# mbed-interface.net
KiCad netlist of a schematic drawn in Altium Designer
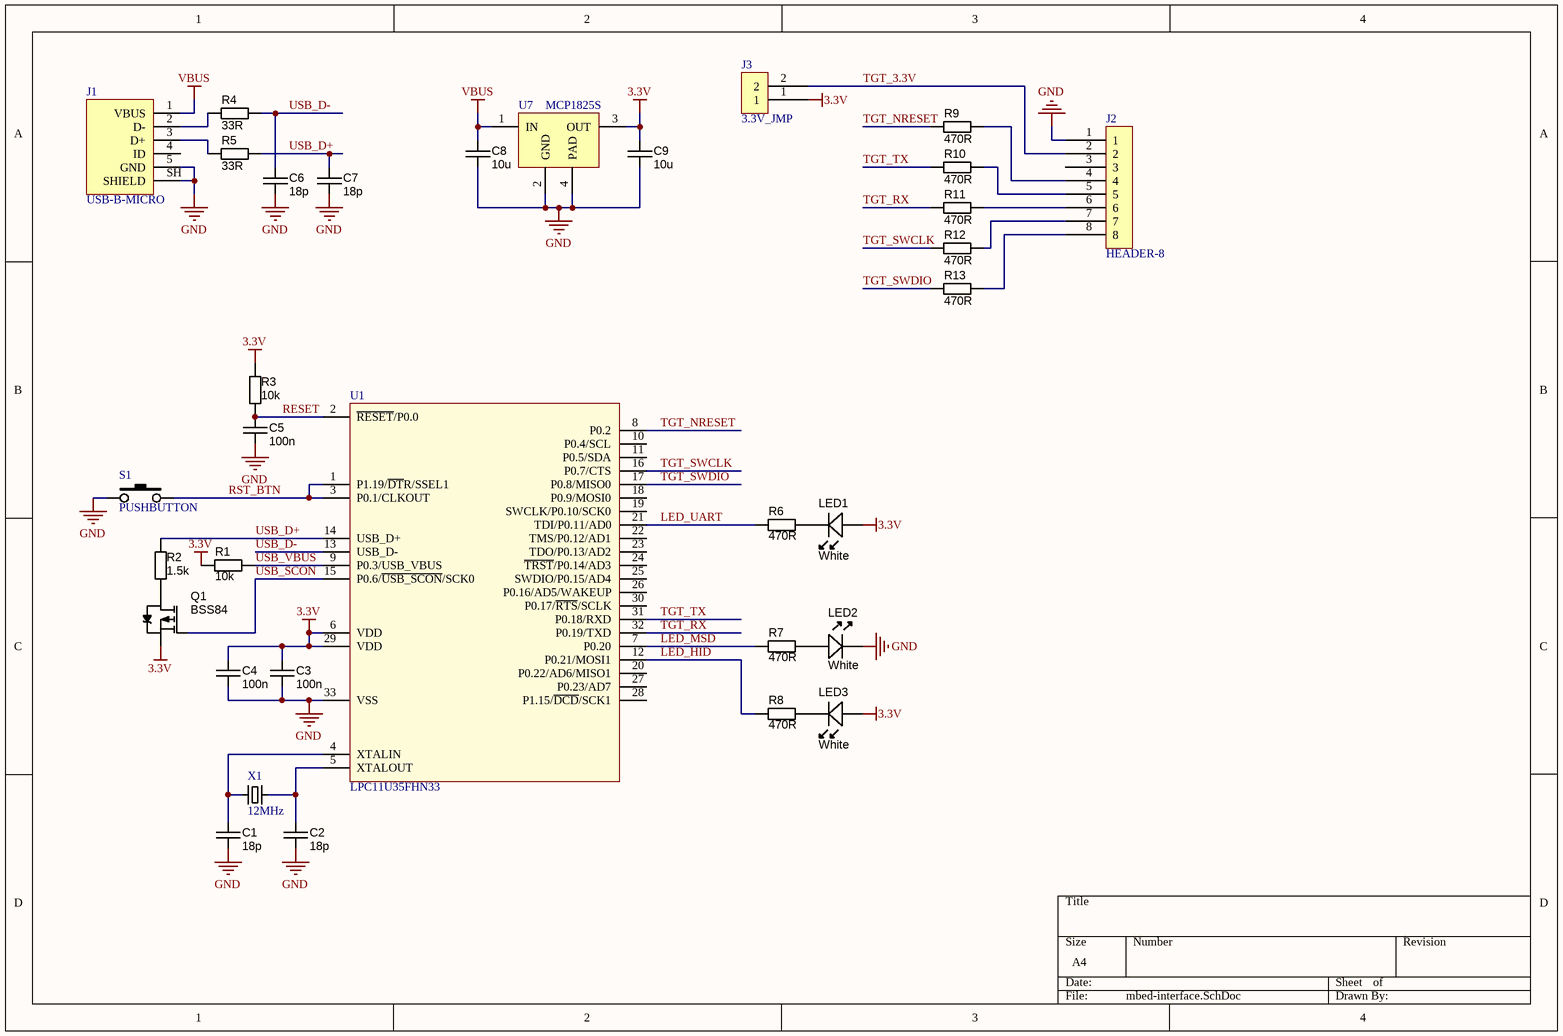
[diagram p0: mbed-interface.SchDoc]

(export (version "E")
  (design (tool "Eeschema 10.0.6"))
  (components
    (comp (ref "C1")
      (value "18p")
      (footprint "CAPC1608X90N")
      (description "Capacitor SMD Cer 8pF ±0.5pF 50V NP0 0603")
      (fields (field (name "TOLERANCE") "±0.5pF"))
      (libsource (lib "PBL - Capacitors") (part "CAPC_8p_0603_NP0_50V"))
    )
    (comp (ref "C2")
      (value "18p")
      (footprint "CAPC1608X90N")
      (description "Capacitor SMD Cer 8pF ±0.5pF 50V NP0 0603")
      (fields (field (name "TOLERANCE") "±0.5pF"))
      (libsource (lib "PBL - Capacitors") (part "CAPC_8p_0603_NP0_50V"))
    )
    (comp (ref "C3")
      (value "100n")
      (footprint "CAPC1608X90N")
      (description "Capacitor SMD Cer 8pF ±0.5pF 50V NP0 0603")
      (fields (field (name "TOLERANCE") "±0.5pF"))
      (libsource (lib "PBL - Capacitors") (part "CAPC_8p_0603_NP0_50V"))
    )
    (comp (ref "C4")
      (value "100n")
      (footprint "CAPC1608X90N")
      (description "Capacitor SMD Cer 8pF ±0.5pF 50V NP0 0603")
      (fields (field (name "TOLERANCE") "±0.5pF"))
      (libsource (lib "PBL - Capacitors") (part "CAPC_8p_0603_NP0_50V"))
    )
    (comp (ref "C5")
      (value "100n")
      (footprint "CAPC1608X90N")
      (description "Capacitor SMD Cer 8pF ±0.5pF 50V NP0 0603")
      (fields (field (name "TOLERANCE") "±0.5pF"))
      (libsource (lib "PBL - Capacitors") (part "CAPC_8p_0603_NP0_50V"))
    )
    (comp (ref "C6")
      (value "18p")
      (footprint "CAPC1608X90N")
      (description "Capacitor SMD Cer 8pF ±0.5pF 50V NP0 0603")
      (fields (field (name "TOLERANCE") "±0.5pF"))
      (libsource (lib "PBL - Capacitors") (part "CAPC_8p_0603_NP0_50V"))
    )
    (comp (ref "C7")
      (value "18p")
      (footprint "CAPC1608X90N")
      (description "Capacitor SMD Cer 8pF ±0.5pF 50V NP0 0603")
      (fields (field (name "TOLERANCE") "±0.5pF"))
      (libsource (lib "PBL - Capacitors") (part "CAPC_8p_0603_NP0_50V"))
    )
    (comp (ref "C8")
      (value "10u")
      (footprint "CAPC3216X180N")
      (description "Capacitor SMD Cer 10uF 10% 10V X5R 1206")
      (fields (field (name "TOLERANCE") "±10%"))
      (libsource (lib "PBL - Capacitors") (part "CAPC_10u_1206_10V"))
    )
    (comp (ref "C9")
      (value "10u")
      (footprint "CAPC3216X180N")
      (description "Capacitor SMD Cer 10uF 10% 10V X5R 1206")
      (fields (field (name "TOLERANCE") "±10%"))
      (libsource (lib "PBL - Capacitors") (part "CAPC_10u_1206_10V"))
    )
    (comp (ref "J1")
      (value "USB-B-MICRO")
      (footprint "USB-B-MICRO-FCI-10104110")
      (libsource (lib "connectors") (part "USB-B-MICRO"))
    )
    (comp (ref "J2")
      (value "HEADER-8")
      (footprint "MICRO-MATCH-8")
      (libsource (lib "connectors") (part "HEADER-8"))
    )
    (comp (ref "J3")
      (value "3.3V_JMP")
      (footprint "PIN-HEADER-2")
      (libsource (lib "connectors") (part "HEADER-2"))
    )
    (comp (ref "LED1")
      (value "White")
      (footprint "LED-0603-WHITE")
      (description "LED 0603 SMD Bright White 8700K")
      (libsource (lib "PBL - Light Sources") (part "LED_SMD_White_0603_Bright"))
    )
    (comp (ref "LED2")
      (value "White")
      (footprint "LED-0603-WHITE")
      (description "LED 0603 SMD Bright White 8700K")
      (libsource (lib "PBL - Light Sources") (part "LED_SMD_White_0603_Bright"))
    )
    (comp (ref "LED3")
      (value "White")
      (footprint "LED-0603-WHITE")
      (description "LED 0603 SMD Bright White 8700K")
      (libsource (lib "PBL - Light Sources") (part "LED_SMD_White_0603_Bright"))
    )
    (comp (ref "Q1")
      (value "BSS84")
      (footprint "SOT23-3")
      (description "MOSFET SMD P-CH 50V 130mA SOT23-3")
      (libsource (lib "PBL - Transistors") (part "MOSFET_BSS84"))
    )
    (comp (ref "R1")
      (value "10k")
      (footprint "RESC1608X55N")
      (description "Resistor SMD chip 1k Ohm 0.1W 1% 0603")
      (fields (field (name "TOLERANCE") "±1%"))
      (libsource (lib "") (part "RES_1K_0603_1%_2"))
    )
    (comp (ref "R2")
      (value "1.5k")
      (footprint "RESC1608X55N")
      (description "Resistor SMD chip 1k Ohm 0.1W 1% 0603")
      (fields (field (name "TOLERANCE") "±1%"))
      (libsource (lib "") (part "RES_1K_0603_1%_1"))
    )
    (comp (ref "R3")
      (value "10k")
      (footprint "RESC1608X55N")
      (description "Resistor SMD chip 1k Ohm 0.1W 1% 0603")
      (fields (field (name "TOLERANCE") "±1%"))
      (libsource (lib "") (part "RES_1K_0603_1%_1"))
    )
    (comp (ref "R4")
      (value "33R")
      (footprint "RESC1608X55N")
      (description "Resistor SMD chip 1k Ohm 0.1W 1% 0603")
      (fields (field (name "TOLERANCE") "±1%"))
      (libsource (lib "PBL - Resistors") (part "RES_1K_0603_1%"))
    )
    (comp (ref "R5")
      (value "33R")
      (footprint "RESC1608X55N")
      (description "Resistor SMD chip 1k Ohm 0.1W 1% 0603")
      (fields (field (name "TOLERANCE") "±1%"))
      (libsource (lib "PBL - Resistors") (part "RES_1K_0603_1%"))
    )
    (comp (ref "R6")
      (value "470R")
      (footprint "RESC1608X55N")
      (description "Resistor SMD chip 1k Ohm 0.1W 1% 0603")
      (fields (field (name "TOLERANCE") "±1%"))
      (libsource (lib "PBL - Resistors") (part "RES_1K_0603_1%"))
    )
    (comp (ref "R7")
      (value "470R")
      (footprint "RESC1608X55N")
      (description "Resistor SMD chip 1k Ohm 0.1W 1% 0603")
      (fields (field (name "TOLERANCE") "±1%"))
      (libsource (lib "PBL - Resistors") (part "RES_1K_0603_1%"))
    )
    (comp (ref "R8")
      (value "470R")
      (footprint "RESC1608X55N")
      (description "Resistor SMD chip 1k Ohm 0.1W 1% 0603")
      (fields (field (name "TOLERANCE") "±1%"))
      (libsource (lib "PBL - Resistors") (part "RES_1K_0603_1%"))
    )
    (comp (ref "R9")
      (value "470R")
      (footprint "RESC1608X55N")
      (description "Resistor SMD chip 1k Ohm 0.1W 1% 0603")
      (fields (field (name "TOLERANCE") "±1%"))
      (libsource (lib "PBL - Resistors") (part "RES_1K_0603_1%"))
    )
    (comp (ref "R10")
      (value "470R")
      (footprint "RESC1608X55N")
      (description "Resistor SMD chip 1k Ohm 0.1W 1% 0603")
      (fields (field (name "TOLERANCE") "±1%"))
      (libsource (lib "PBL - Resistors") (part "RES_1K_0603_1%"))
    )
    (comp (ref "R11")
      (value "470R")
      (footprint "RESC1608X55N")
      (description "Resistor SMD chip 1k Ohm 0.1W 1% 0603")
      (fields (field (name "TOLERANCE") "±1%"))
      (libsource (lib "PBL - Resistors") (part "RES_1K_0603_1%"))
    )
    (comp (ref "R12")
      (value "470R")
      (footprint "RESC1608X55N")
      (description "Resistor SMD chip 1k Ohm 0.1W 1% 0603")
      (fields (field (name "TOLERANCE") "±1%"))
      (libsource (lib "PBL - Resistors") (part "RES_1K_0603_1%"))
    )
    (comp (ref "R13")
      (value "470R")
      (footprint "RESC1608X55N")
      (description "Resistor SMD chip 1k Ohm 0.1W 1% 0603")
      (fields (field (name "TOLERANCE") "±1%"))
      (libsource (lib "PBL - Resistors") (part "RES_1K_0603_1%"))
    )
    (comp (ref "S1")
      (value "PUSHBUTTON")
      (footprint "KMR421NGLFS")
      (libsource (lib "switches") (part "PUSHBUTTON"))
    )
    (comp (ref "U1")
      (value "LPC11U35FHN33")
      (footprint "HVQFN33")
      (libsource (lib "nxp") (part "LPC11U35FHN33"))
    )
    (comp (ref "U7")
      (value "MCP1825S")
      (footprint "SOT230P700X180-4N")
      (libsource (lib "power") (part "MIC5239"))
    )
    (comp (ref "X1")
      (value "12MHz")
      (footprint "XTAL-3.2x2.5")
      (libsource (lib "misc") (part "XTAL-3.2X2.5"))
    )
  )
  (nets
    (net (code "1") (name "/LED_HID") (class "Default")
      (node (ref "R8") (pin "1") (pinfunction "1_1") (pintype "passive"))
      (node (ref "U1") (pin "12") (pinfunction "P0.21/MOSI1_12") (pintype "passive"))
    )
    (net (code "2") (name "/LED_MSD") (class "Default")
      (node (ref "R7") (pin "1") (pinfunction "1_1") (pintype "passive"))
      (node (ref "U1") (pin "7") (pinfunction "P0.20_7") (pintype "passive"))
    )
    (net (code "3") (name "/LED_UART") (class "Default")
      (node (ref "R6") (pin "1") (pinfunction "1_1") (pintype "passive"))
      (node (ref "U1") (pin "21") (pinfunction "TDI/P0.11/AD0_21") (pintype "passive"))
    )
    (net (code "4") (name "/RESET") (class "Default")
      (node (ref "C5") (pin "1") (pintype "passive"))
      (node (ref "R3") (pin "2") (pinfunction "2_2") (pintype "passive"))
      (node (ref "U1") (pin "2") (pinfunction "~{RESET}/P0.0_2") (pintype "passive"))
    )
    (net (code "5") (name "/RST_BTN") (class "Default")
      (node (ref "S1") (pin "2") (pintype "passive"))
      (node (ref "U1") (pin "1") (pinfunction "P1.19/~{DT}R/SSEL1_1") (pintype "passive"))
      (node (ref "U1") (pin "3") (pinfunction "P0.1/CLKOUT_3") (pintype "passive"))
    )
    (net (code "6") (name "/TGT_3.3V") (class "Default")
      (node (ref "J2") (pin "2") (pinfunction "2_2") (pintype "passive"))
      (node (ref "J3") (pin "2") (pinfunction "2_2") (pintype "passive"))
    )
    (net (code "7") (name "/TGT_NRESET") (class "Default")
      (node (ref "R9") (pin "1") (pinfunction "1_1") (pintype "passive"))
      (node (ref "U1") (pin "8") (pinfunction "P0.2_8") (pintype "passive"))
    )
    (net (code "8") (name "/TGT_RX") (class "Default")
      (node (ref "R11") (pin "1") (pinfunction "1_1") (pintype "passive"))
      (node (ref "U1") (pin "32") (pinfunction "P0.19/TXD_32") (pintype "passive"))
    )
    (net (code "9") (name "/TGT_SWCLK") (class "Default")
      (node (ref "R12") (pin "1") (pinfunction "1_1") (pintype "passive"))
      (node (ref "U1") (pin "16") (pinfunction "P0.7/CTS_16") (pintype "passive"))
    )
    (net (code "10") (name "/TGT_SWDIO") (class "Default")
      (node (ref "R13") (pin "1") (pinfunction "1_1") (pintype "passive"))
      (node (ref "U1") (pin "17") (pinfunction "P0.8/MISO0_17") (pintype "passive"))
    )
    (net (code "11") (name "/TGT_TX") (class "Default")
      (node (ref "R10") (pin "1") (pinfunction "1_1") (pintype "passive"))
      (node (ref "U1") (pin "31") (pinfunction "P0.18/RXD_31") (pintype "passive"))
    )
    (net (code "12") (name "/USB_D+") (class "Default")
      (node (ref "C7") (pin "1") (pintype "passive"))
      (node (ref "R2") (pin "1") (pinfunction "1_1") (pintype "passive"))
      (node (ref "R5") (pin "2") (pinfunction "2_2") (pintype "passive"))
      (node (ref "U1") (pin "14") (pinfunction "USB_D+_14") (pintype "passive"))
    )
    (net (code "13") (name "/USB_D-") (class "Default")
      (node (ref "C6") (pin "1") (pintype "passive"))
      (node (ref "R4") (pin "2") (pinfunction "2_2") (pintype "passive"))
      (node (ref "U1") (pin "13") (pinfunction "USB_D-_13") (pintype "passive"))
    )
    (net (code "14") (name "/USB_SCON") (class "Default")
      (node (ref "Q1") (pin "1") (pinfunction "G_1") (pintype "passive"))
      (node (ref "U1") (pin "15") (pinfunction "P0.6/~{USB_SCON}/SCK0_15") (pintype "passive"))
    )
    (net (code "15") (name "/USB_VBUS") (class "Default")
      (node (ref "R1") (pin "1") (pinfunction "1_1") (pintype "passive"))
      (node (ref "U1") (pin "9") (pinfunction "P0.3/USB_VBUS_9") (pintype "passive"))
    )
    (net (code "16") (name "3.3V") (class "Default")
      (node (ref "C3") (pin "1") (pintype "passive"))
      (node (ref "C4") (pin "1") (pintype "passive"))
      (node (ref "C9") (pin "1") (pintype "passive"))
      (node (ref "J3") (pin "1") (pinfunction "1_1") (pintype "passive"))
      (node (ref "LED1") (pin "A") (pinfunction "A_A") (pintype "passive"))
      (node (ref "LED3") (pin "A") (pinfunction "A_A") (pintype "passive"))
      (node (ref "Q1") (pin "2") (pinfunction "S_2") (pintype "passive"))
      (node (ref "R1") (pin "2") (pinfunction "2_2") (pintype "passive"))
      (node (ref "R3") (pin "1") (pinfunction "1_1") (pintype "passive"))
      (node (ref "U1") (pin "29") (pinfunction "VDD_29") (pintype "passive"))
      (node (ref "U1") (pin "6") (pinfunction "VDD_6") (pintype "passive"))
      (node (ref "U7") (pin "3") (pinfunction "OUT_3") (pintype "power_in"))
    )
    (net (code "17") (name "GND") (class "Default")
      (node (ref "C1") (pin "2") (pintype "passive"))
      (node (ref "C2") (pin "2") (pintype "passive"))
      (node (ref "C3") (pin "2") (pintype "passive"))
      (node (ref "C4") (pin "2") (pintype "passive"))
      (node (ref "C5") (pin "2") (pintype "passive"))
      (node (ref "C6") (pin "2") (pintype "passive"))
      (node (ref "C7") (pin "2") (pintype "passive"))
      (node (ref "C8") (pin "2") (pintype "passive"))
      (node (ref "C9") (pin "2") (pintype "passive"))
      (node (ref "J1") (pin "5") (pinfunction "GND_5") (pintype "passive"))
      (node (ref "J1") (pin "SH") (pinfunction "SHIELD_SH") (pintype "passive"))
      (node (ref "J2") (pin "1") (pinfunction "1_1") (pintype "passive"))
      (node (ref "LED2") (pin "K") (pinfunction "K_K") (pintype "passive"))
      (node (ref "S1") (pin "1") (pintype "passive"))
      (node (ref "U1") (pin "33") (pinfunction "VSS_33") (pintype "passive"))
      (node (ref "U7") (pin "2") (pinfunction "GND_2") (pintype "power_in"))
      (node (ref "U7") (pin "4") (pinfunction "PAD_4") (pintype "power_in"))
    )
    (net (code "18") (name "Net-(J1-D+)") (class "Default")
      (node (ref "J1") (pin "3") (pinfunction "D+_3") (pintype "passive"))
      (node (ref "R5") (pin "1") (pinfunction "1_1") (pintype "passive"))
    )
    (net (code "19") (name "Net-(J1-D-)") (class "Default")
      (node (ref "J1") (pin "2") (pinfunction "D-_2") (pintype "passive"))
      (node (ref "R4") (pin "1") (pinfunction "1_1") (pintype "passive"))
    )
    (net (code "20") (name "Net-(J2-Pad4)") (class "Default")
      (node (ref "J2") (pin "4") (pinfunction "4_4") (pintype "passive"))
      (node (ref "R9") (pin "2") (pinfunction "2_2") (pintype "passive"))
    )
    (net (code "21") (name "Net-(J2-Pad5)") (class "Default")
      (node (ref "J2") (pin "5") (pinfunction "5_5") (pintype "passive"))
      (node (ref "R10") (pin "2") (pinfunction "2_2") (pintype "passive"))
    )
    (net (code "22") (name "Net-(J2-Pad6)") (class "Default")
      (node (ref "J2") (pin "6") (pinfunction "6_6") (pintype "passive"))
      (node (ref "R11") (pin "2") (pinfunction "2_2") (pintype "passive"))
    )
    (net (code "23") (name "Net-(J2-Pad7)") (class "Default")
      (node (ref "J2") (pin "7") (pinfunction "7_7") (pintype "passive"))
      (node (ref "R12") (pin "2") (pinfunction "2_2") (pintype "passive"))
    )
    (net (code "24") (name "Net-(J2-Pad8)") (class "Default")
      (node (ref "J2") (pin "8") (pinfunction "8_8") (pintype "passive"))
      (node (ref "R13") (pin "2") (pinfunction "2_2") (pintype "passive"))
    )
    (net (code "25") (name "Net-(LED1-PadK)") (class "Default")
      (node (ref "LED1") (pin "K") (pinfunction "K_K") (pintype "passive"))
      (node (ref "R6") (pin "2") (pinfunction "2_2") (pintype "passive"))
    )
    (net (code "26") (name "Net-(LED2-PadA)") (class "Default")
      (node (ref "LED2") (pin "A") (pinfunction "A_A") (pintype "passive"))
      (node (ref "R7") (pin "2") (pinfunction "2_2") (pintype "passive"))
    )
    (net (code "27") (name "Net-(LED3-PadK)") (class "Default")
      (node (ref "LED3") (pin "K") (pinfunction "K_K") (pintype "passive"))
      (node (ref "R8") (pin "2") (pinfunction "2_2") (pintype "passive"))
    )
    (net (code "28") (name "Net-(Q1-D)") (class "Default")
      (node (ref "Q1") (pin "3") (pinfunction "D_3") (pintype "passive"))
      (node (ref "R2") (pin "2") (pinfunction "2_2") (pintype "passive"))
    )
    (net (code "29") (name "Net-(U1-XTALIN)") (class "Default")
      (node (ref "C1") (pin "1") (pintype "passive"))
      (node (ref "U1") (pin "4") (pinfunction "XTALIN_4") (pintype "passive"))
      (node (ref "X1") (pin "1") (pinfunction "1_1") (pintype "passive"))
    )
    (net (code "30") (name "Net-(U1-XTALOUT)") (class "Default")
      (node (ref "C2") (pin "1") (pintype "passive"))
      (node (ref "U1") (pin "5") (pinfunction "XTALOUT_5") (pintype "passive"))
      (node (ref "X1") (pin "3") (pinfunction "3_3") (pintype "passive"))
    )
    (net (code "31") (name "VBUS") (class "Default")
      (node (ref "C8") (pin "1") (pintype "passive"))
      (node (ref "J1") (pin "1") (pinfunction "VBUS_1") (pintype "passive"))
      (node (ref "U7") (pin "1") (pinfunction "IN_1") (pintype "power_in"))
    )
    (net (code "32") (name "unconnected-(J1-ID-Pad4)") (class "Default")
      (node (ref "J1") (pin "4") (pinfunction "ID_4") (pintype "passive"))
    )
    (net (code "33") (name "unconnected-(J2-Pad3)") (class "Default")
      (node (ref "J2") (pin "3") (pinfunction "3_3") (pintype "passive"))
    )
    (net (code "34") (name "unconnected-(U1-P0.4{slash}SCL-Pad10)") (class "Default")
      (node (ref "U1") (pin "10") (pinfunction "P0.4/SCL_10") (pintype "passive"))
    )
    (net (code "35") (name "unconnected-(U1-P0.5{slash}SDA-Pad11)") (class "Default")
      (node (ref "U1") (pin "11") (pinfunction "P0.5/SDA_11") (pintype "passive"))
    )
    (net (code "36") (name "unconnected-(U1-P0.9{slash}MOSI0-Pad18)") (class "Default")
      (node (ref "U1") (pin "18") (pinfunction "P0.9/MOSI0_18") (pintype "passive"))
    )
    (net (code "37") (name "unconnected-(U1-P0.16{slash}AD5{slash}WAKEUP-Pad26)") (class "Default")
      (node (ref "U1") (pin "26") (pinfunction "P0.16/AD5/WAKEUP_26") (pintype "passive"))
    )
    (net (code "38") (name "unconnected-(U1-P0.17{slash}~{RTS}{slash}SCLK-Pad30)") (class "Default")
      (node (ref "U1") (pin "30") (pinfunction "P0.17/~{RTS}/SCLK_30") (pintype "passive"))
    )
    (net (code "39") (name "unconnected-(U1-P0.22{slash}AD6{slash}MISO1-Pad20)") (class "Default")
      (node (ref "U1") (pin "20") (pinfunction "P0.22/AD6/MISO1_20") (pintype "passive"))
    )
    (net (code "40") (name "unconnected-(U1-P0.23{slash}AD7-Pad27)") (class "Default")
      (node (ref "U1") (pin "27") (pinfunction "P0.23/AD7_27") (pintype "passive"))
    )
    (net (code "41") (name "unconnected-(U1-P1.15{slash}~{DCD}{slash}SCK1-Pad28)") (class "Default")
      (node (ref "U1") (pin "28") (pinfunction "P1.15/~{DCD}/SCK1_28") (pintype "passive"))
    )
    (net (code "42") (name "unconnected-(U1-SWCLK{slash}P0.10{slash}SCK0-Pad19)") (class "Default")
      (node (ref "U1") (pin "19") (pinfunction "SWCLK/P0.10/SCK0_19") (pintype "passive"))
    )
    (net (code "43") (name "unconnected-(U1-SWDIO{slash}P0.15{slash}AD4-Pad25)") (class "Default")
      (node (ref "U1") (pin "25") (pinfunction "SWDIO/P0.15/AD4_25") (pintype "passive"))
    )
    (net (code "44") (name "unconnected-(U1-TDO{slash}P0.13{slash}AD2-Pad23)") (class "Default")
      (node (ref "U1") (pin "23") (pinfunction "TDO/P0.13/AD2_23") (pintype "passive"))
    )
    (net (code "45") (name "unconnected-(U1-TMS{slash}P0.12{slash}AD1-Pad22)") (class "Default")
      (node (ref "U1") (pin "22") (pinfunction "TMS/P0.12/AD1_22") (pintype "passive"))
    )
    (net (code "46") (name "unconnected-(U1-~{TRST}{slash}P0.14{slash}AD3-Pad24)") (class "Default")
      (node (ref "U1") (pin "24") (pinfunction "~{TRST}/P0.14/AD3_24") (pintype "passive"))
    )
  )
)
